# ADC.net
KiCad netlist of a schematic drawn in Altium Designer
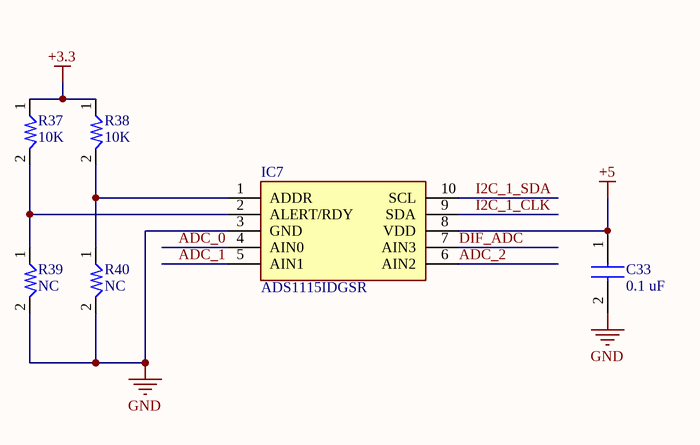
[diagram p0: ADC.SchDoc]

(export (version "E")
  (design (tool "Eeschema 10.0.6"))
  (components
    (comp (ref "C33")
      (value "0.1 uF")
      (footprint "CAP0603")
      (description "Capacitor")
      (fields
        (field (name "MANUFACTURER_PART_NUMBER") "CC0603KRX7R9BB104")
        (field (name "MOUSER PART NUMBER") "603-CC603KRX7R9BB104")
      )
      (libsource (lib "Valve_Controller_Lib") (part "CC0603KRX7R9BB104"))
    )
    (comp (ref "IC7")
      (value "ADS1115IDGSR")
      (footprint "SamacSys:SOP50P490X110-10N")
      (description "Integrated Circuit")
      (fields (field (name "MOUSER PART NUMBER") "595-ADS1115IDGSR"))
      (libsource (lib "*") (part "ADS1115IDGSR"))
    )
    (comp (ref "R37")
      (value "10K")
      (footprint "RES0603")
      (description "Resistor")
      (fields (field (name "MANUFACTURER_PART_NUMBER") "0603WAF1001T5E"))
      (libsource (lib "Valve_Controller_Lib") (part "RES"))
    )
    (comp (ref "R38")
      (value "10K")
      (footprint "RES0603")
      (description "Resistor")
      (fields (field (name "MANUFACTURER_PART_NUMBER") "0603WAF1001T5E"))
      (libsource (lib "Valve_Controller_Lib") (part "RES"))
    )
    (comp (ref "R39")
      (value "NC")
      (footprint "RES0603")
      (description "Resistor")
      (fields (field (name "MANUFACTURER_PART_NUMBER") "0603WAF1001T5E"))
      (libsource (lib "Valve_Controller_Lib") (part "RES"))
    )
    (comp (ref "R40")
      (value "NC")
      (footprint "RES0603")
      (description "Resistor")
      (fields (field (name "MANUFACTURER_PART_NUMBER") "0603WAF1001T5E"))
      (libsource (lib "Valve_Controller_Lib") (part "RES"))
    )
  )
  (nets
    (net (code "1") (name "+3.3") (class "Default")
      (node (ref "R37") (pin "1") (pinfunction "1_1") (pintype "passive"))
      (node (ref "R38") (pin "1") (pinfunction "1_1") (pintype "passive"))
    )
    (net (code "2") (name "+5") (class "Default")
      (node (ref "C33") (pin "1") (pinfunction "1_1") (pintype "passive"))
      (node (ref "IC7") (pin "8") (pinfunction "VDD_8") (pintype "passive"))
    )
    (net (code "3") (name "/ADC_0") (class "Default")
      (node (ref "IC7") (pin "4") (pinfunction "AIN0_4") (pintype "passive"))
    )
    (net (code "4") (name "/ADC_1") (class "Default")
      (node (ref "IC7") (pin "5") (pinfunction "AIN1_5") (pintype "passive"))
    )
    (net (code "5") (name "/ADC_2") (class "Default")
      (node (ref "IC7") (pin "6") (pinfunction "AIN2_6") (pintype "passive"))
    )
    (net (code "6") (name "/DIF_ADC") (class "Default")
      (node (ref "IC7") (pin "7") (pinfunction "AIN3_7") (pintype "passive"))
    )
    (net (code "7") (name "/I2C_1_CLK") (class "Default")
      (node (ref "IC7") (pin "9") (pinfunction "SDA_9") (pintype "passive"))
    )
    (net (code "8") (name "/I2C_1_SDA") (class "Default")
      (node (ref "IC7") (pin "10") (pinfunction "SCL_10") (pintype "passive"))
    )
    (net (code "9") (name "GND") (class "Default")
      (node (ref "C33") (pin "2") (pinfunction "2_2") (pintype "passive"))
      (node (ref "IC7") (pin "3") (pinfunction "GND_3") (pintype "passive"))
      (node (ref "R39") (pin "2") (pinfunction "2_2") (pintype "passive"))
      (node (ref "R40") (pin "2") (pinfunction "2_2") (pintype "passive"))
    )
    (net (code "10") (name "Net-(IC7-ADDR)") (class "Default")
      (node (ref "IC7") (pin "1") (pinfunction "ADDR_1") (pintype "passive"))
      (node (ref "R38") (pin "2") (pinfunction "2_2") (pintype "passive"))
      (node (ref "R40") (pin "1") (pinfunction "1_1") (pintype "passive"))
    )
    (net (code "11") (name "Net-(IC7-ALERT{slash}RDY)") (class "Default")
      (node (ref "IC7") (pin "2") (pinfunction "ALERT/RDY_2") (pintype "passive"))
      (node (ref "R37") (pin "2") (pinfunction "2_2") (pintype "passive"))
      (node (ref "R39") (pin "1") (pinfunction "1_1") (pintype "passive"))
    )
  )
)
